# A601.net
KiCad netlist of a schematic drawn in EAGLE
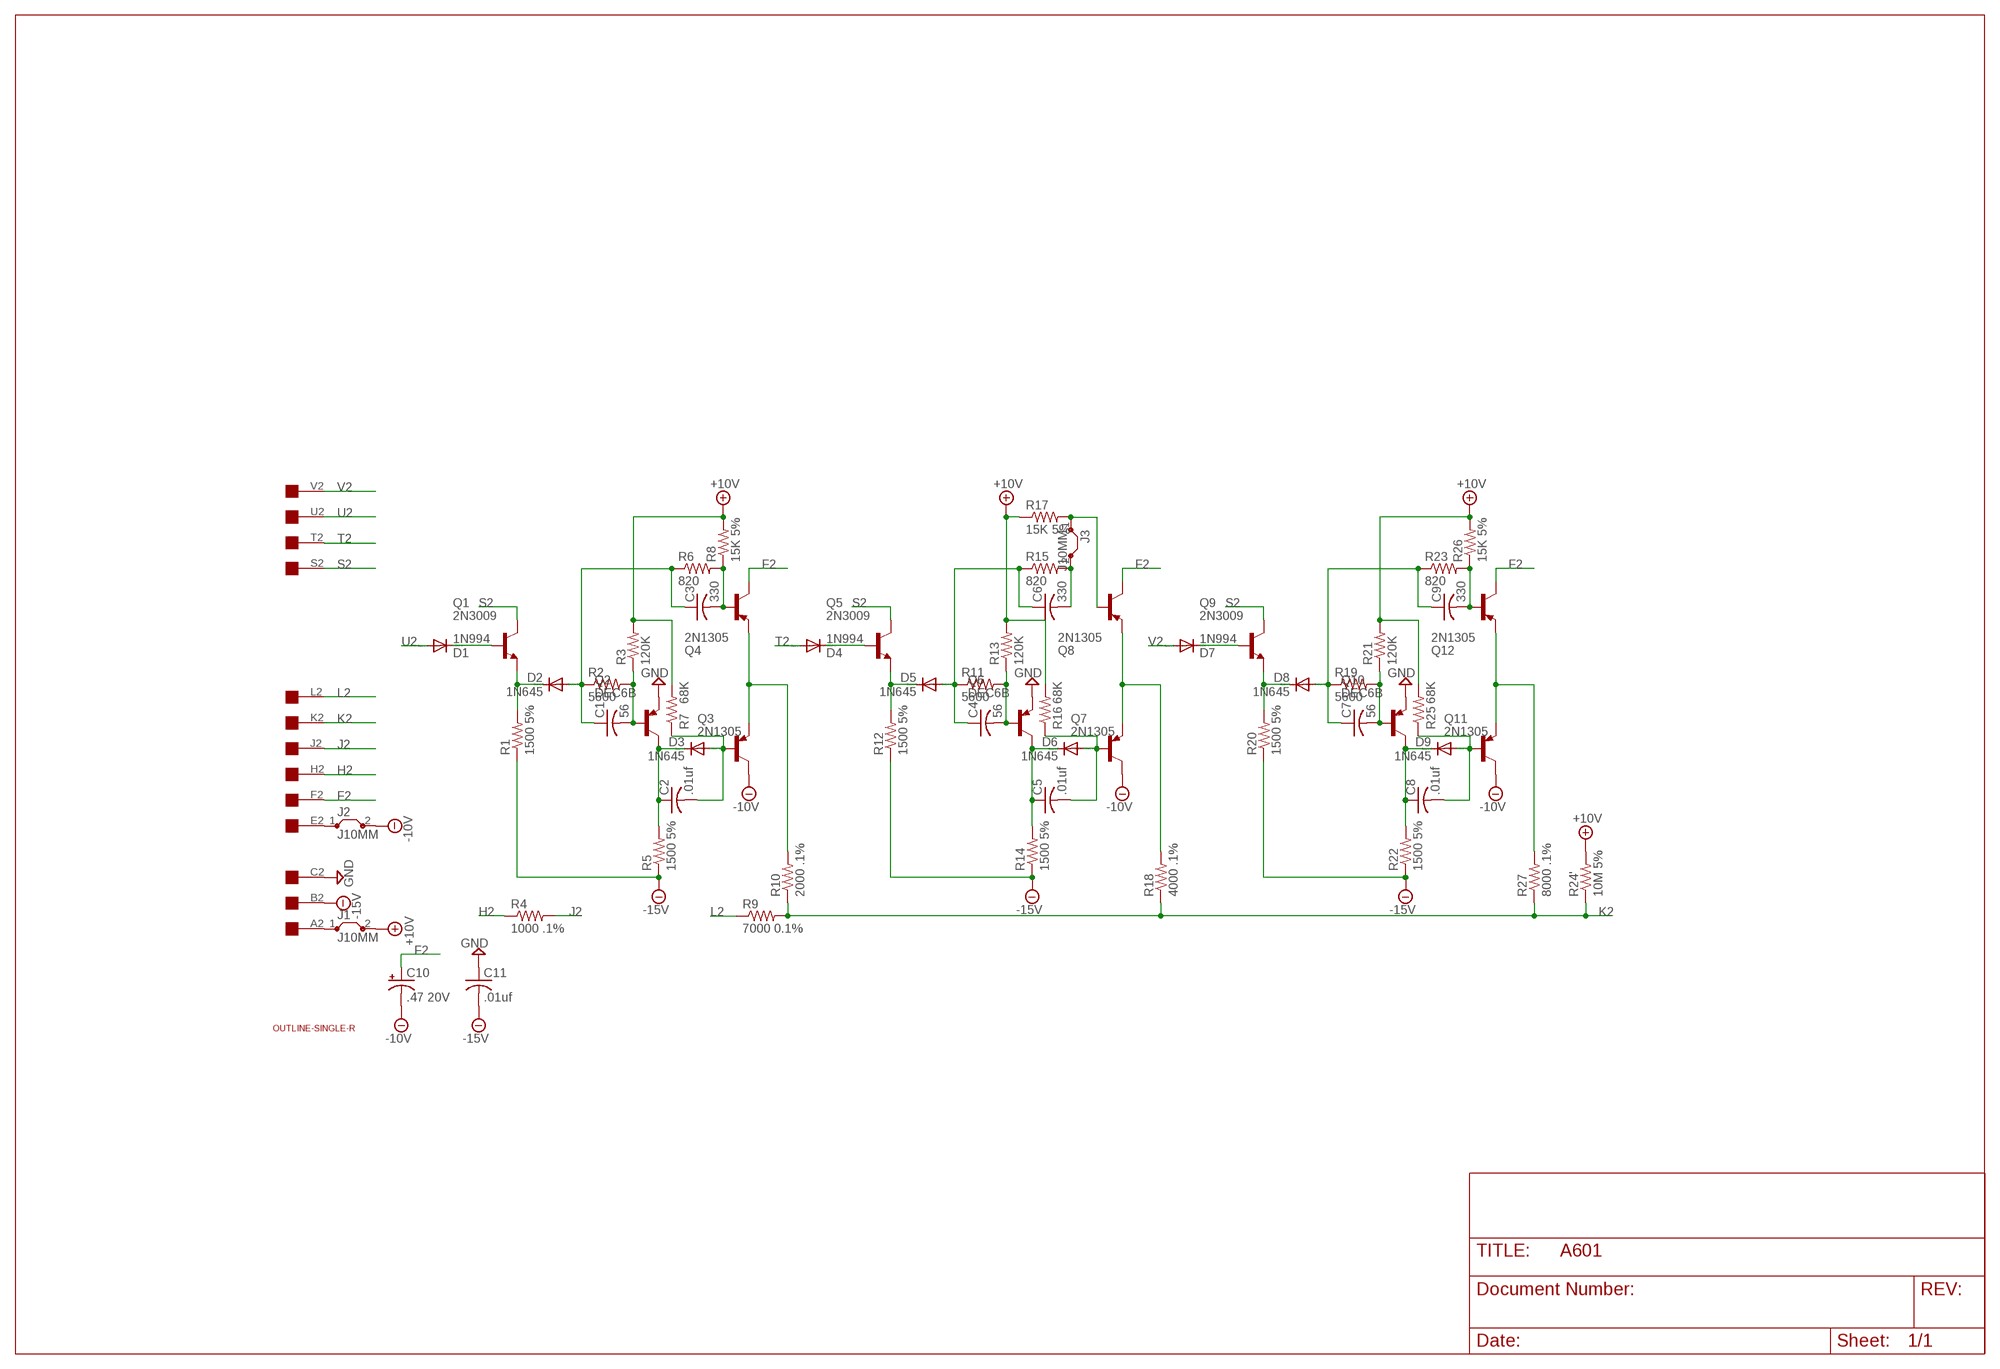
[diagram p0: schematic, sheet 1]

(export (version "E")
  (design (tool "Eeschema 10.0.6"))
  (components
    (comp (ref "C1")
      (value "56")
      (footprint "eagle-import:C075-032X103")
      (libsource (lib "eagle-import") (part "C-US075-032X103"))
    )
    (comp (ref "C2")
      (value ".01uf")
      (footprint "eagle-import:C050-025X075")
      (libsource (lib "eagle-import") (part "C-US050-025X075"))
    )
    (comp (ref "C3")
      (value "330")
      (footprint "eagle-import:C102-043X133")
      (libsource (lib "eagle-import") (part "C-US102-043X133"))
    )
    (comp (ref "C4")
      (value "56")
      (footprint "eagle-import:C075-032X103")
      (libsource (lib "eagle-import") (part "C-US075-032X103"))
    )
    (comp (ref "C5")
      (value ".01uf")
      (footprint "eagle-import:C050-025X075")
      (libsource (lib "eagle-import") (part "C-US050-025X075"))
    )
    (comp (ref "C6")
      (value "330")
      (footprint "eagle-import:C102-043X133")
      (libsource (lib "eagle-import") (part "C-US102-043X133"))
    )
    (comp (ref "C7")
      (value "56")
      (footprint "eagle-import:C075-032X103")
      (libsource (lib "eagle-import") (part "C-US075-032X103"))
    )
    (comp (ref "C8")
      (value ".01uf")
      (footprint "eagle-import:C050-025X075")
      (libsource (lib "eagle-import") (part "C-US050-025X075"))
    )
    (comp (ref "C9")
      (value "330")
      (footprint "eagle-import:C102-043X133")
      (libsource (lib "eagle-import") (part "C-US102-043X133"))
    )
    (comp (ref "C10")
      (value ".47 20V")
      (footprint "eagle-import:E22-6")
      (libsource (lib "eagle-import") (part "CPOL-USE22-6AXIAL"))
    )
    (comp (ref "C11")
      (value ".01uf")
      (footprint "eagle-import:C050-025X075")
      (libsource (lib "eagle-import") (part "C-US050-025X075"))
    )
    (comp (ref "D1")
      (value "1N994")
      (footprint "eagle-import:DO35-10")
      (libsource (lib "eagle-import") (part "1N4148DO35-10"))
    )
    (comp (ref "D2")
      (value "1N645")
      (footprint "eagle-import:DO35-10")
      (libsource (lib "eagle-import") (part "1N4148DO35-10"))
    )
    (comp (ref "D3")
      (value "1N645")
      (footprint "eagle-import:DO35-10")
      (libsource (lib "eagle-import") (part "1N4148DO35-10"))
    )
    (comp (ref "D4")
      (value "1N994")
      (footprint "eagle-import:DO35-10")
      (libsource (lib "eagle-import") (part "1N4148DO35-10"))
    )
    (comp (ref "D5")
      (value "1N645")
      (footprint "eagle-import:DO35-10")
      (libsource (lib "eagle-import") (part "1N4148DO35-10"))
    )
    (comp (ref "D6")
      (value "1N645")
      (footprint "eagle-import:DO35-10")
      (libsource (lib "eagle-import") (part "1N4148DO35-10"))
    )
    (comp (ref "D7")
      (value "1N994")
      (footprint "eagle-import:DO35-10")
      (libsource (lib "eagle-import") (part "1N4148DO35-10"))
    )
    (comp (ref "D8")
      (value "1N645")
      (footprint "eagle-import:DO35-10")
      (libsource (lib "eagle-import") (part "1N4148DO35-10"))
    )
    (comp (ref "D9")
      (value "1N645")
      (footprint "eagle-import:DO35-10")
      (libsource (lib "eagle-import") (part "1N4148DO35-10"))
    )
    (comp (ref "J1")
      (value "J10MM")
      (footprint "eagle-import:10")
      (libsource (lib "eagle-import") (part "J10MM"))
    )
    (comp (ref "J2")
      (value "J10MM")
      (footprint "eagle-import:10")
      (libsource (lib "eagle-import") (part "J10MM"))
    )
    (comp (ref "J3")
      (value "J10MM")
      (footprint "eagle-import:10")
      (libsource (lib "eagle-import") (part "J10MM"))
    )
    (comp (ref "Q1")
      (value "2N3009")
      (footprint "eagle-import:TO39")
      (libsource (lib "eagle-import") (part "-NPN-TO39-EBC2N1613"))
    )
    (comp (ref "Q2")
      (value "DEC6B")
      (footprint "eagle-import:TO39")
      (libsource (lib "eagle-import") (part "2N2904A"))
    )
    (comp (ref "Q3")
      (value "2N1305")
      (footprint "eagle-import:TO39")
      (libsource (lib "eagle-import") (part "2N2904A"))
    )
    (comp (ref "Q4")
      (value "2N1305")
      (footprint "eagle-import:TO39")
      (libsource (lib "eagle-import") (part "2N2904A"))
    )
    (comp (ref "Q5")
      (value "2N3009")
      (footprint "eagle-import:TO39")
      (libsource (lib "eagle-import") (part "-NPN-TO39-EBC2N1613"))
    )
    (comp (ref "Q6")
      (value "DEC6B")
      (footprint "eagle-import:TO39")
      (libsource (lib "eagle-import") (part "2N2904A"))
    )
    (comp (ref "Q7")
      (value "2N1305")
      (footprint "eagle-import:TO39")
      (libsource (lib "eagle-import") (part "2N2904A"))
    )
    (comp (ref "Q8")
      (value "2N1305")
      (footprint "eagle-import:TO39")
      (libsource (lib "eagle-import") (part "2N2904A"))
    )
    (comp (ref "Q9")
      (value "2N3009")
      (footprint "eagle-import:TO39")
      (libsource (lib "eagle-import") (part "-NPN-TO39-EBC2N1613"))
    )
    (comp (ref "Q10")
      (value "DEC6B")
      (footprint "eagle-import:TO39")
      (libsource (lib "eagle-import") (part "2N2904A"))
    )
    (comp (ref "Q11")
      (value "2N1305")
      (footprint "eagle-import:TO39")
      (libsource (lib "eagle-import") (part "2N2904A"))
    )
    (comp (ref "Q12")
      (value "2N1305")
      (footprint "eagle-import:TO39")
      (libsource (lib "eagle-import") (part "2N2904A"))
    )
    (comp (ref "R1")
      (value "1500 5%")
      (footprint "eagle-import:0207_10")
      (libsource (lib "eagle-import") (part "R-US_0207/10"))
    )
    (comp (ref "R2")
      (value "5600")
      (footprint "eagle-import:0207_10")
      (libsource (lib "eagle-import") (part "R-US_0207/10"))
    )
    (comp (ref "R3")
      (value "120K")
      (footprint "eagle-import:0207_10")
      (libsource (lib "eagle-import") (part "R-US_0207/10"))
    )
    (comp (ref "R4")
      (value "1000 .1%")
      (footprint "eagle-import:0309_12")
      (libsource (lib "eagle-import") (part "R-US_0309/12"))
    )
    (comp (ref "R5")
      (value "1500 5%")
      (footprint "eagle-import:0207_10")
      (libsource (lib "eagle-import") (part "R-US_0207/10"))
    )
    (comp (ref "R6")
      (value "820")
      (footprint "eagle-import:0207_10")
      (libsource (lib "eagle-import") (part "R-US_0207/10"))
    )
    (comp (ref "R7")
      (value "68K")
      (footprint "eagle-import:0207_10")
      (libsource (lib "eagle-import") (part "R-US_0207/10"))
    )
    (comp (ref "R8")
      (value "15K 5%")
      (footprint "eagle-import:0207_10")
      (libsource (lib "eagle-import") (part "R-US_0207/10"))
    )
    (comp (ref "R9")
      (value "7000 0.1%")
      (footprint "eagle-import:0309_12")
      (libsource (lib "eagle-import") (part "R-US_0309/12"))
    )
    (comp (ref "R10")
      (value "2000 .1%")
      (footprint "eagle-import:0309_12")
      (libsource (lib "eagle-import") (part "R-US_0309/12"))
    )
    (comp (ref "R11")
      (value "5600")
      (footprint "eagle-import:0207_10")
      (libsource (lib "eagle-import") (part "R-US_0207/10"))
    )
    (comp (ref "R12")
      (value "1500 5%")
      (footprint "eagle-import:0207_10")
      (libsource (lib "eagle-import") (part "R-US_0207/10"))
    )
    (comp (ref "R13")
      (value "120K")
      (footprint "eagle-import:0207_10")
      (libsource (lib "eagle-import") (part "R-US_0207/10"))
    )
    (comp (ref "R14")
      (value "1500 5%")
      (footprint "eagle-import:0207_10")
      (libsource (lib "eagle-import") (part "R-US_0207/10"))
    )
    (comp (ref "R15")
      (value "820")
      (footprint "eagle-import:0207_10")
      (libsource (lib "eagle-import") (part "R-US_0207/10"))
    )
    (comp (ref "R16")
      (value "68K")
      (footprint "eagle-import:0207_10")
      (libsource (lib "eagle-import") (part "R-US_0207/10"))
    )
    (comp (ref "R17")
      (value "15K 5%")
      (footprint "eagle-import:0207_10")
      (libsource (lib "eagle-import") (part "R-US_0207/10"))
    )
    (comp (ref "R18")
      (value "4000 .1%")
      (footprint "eagle-import:0309_12")
      (libsource (lib "eagle-import") (part "R-US_0309/12"))
    )
    (comp (ref "R19")
      (value "5600")
      (footprint "eagle-import:0207_10")
      (libsource (lib "eagle-import") (part "R-US_0207/10"))
    )
    (comp (ref "R20")
      (value "1500 5%")
      (footprint "eagle-import:0207_10")
      (libsource (lib "eagle-import") (part "R-US_0207/10"))
    )
    (comp (ref "R21")
      (value "120K")
      (footprint "eagle-import:0207_10")
      (libsource (lib "eagle-import") (part "R-US_0207/10"))
    )
    (comp (ref "R22")
      (value "1500 5%")
      (footprint "eagle-import:0207_10")
      (libsource (lib "eagle-import") (part "R-US_0207/10"))
    )
    (comp (ref "R23")
      (value "820")
      (footprint "eagle-import:0207_10")
      (libsource (lib "eagle-import") (part "R-US_0207/10"))
    )
    (comp (ref "R24'")
      (value "10M 5%")
      (footprint "eagle-import:0207_10")
      (libsource (lib "eagle-import") (part "R-US_0207/10"))
    )
    (comp (ref "R25")
      (value "68K")
      (footprint "eagle-import:0207_10")
      (libsource (lib "eagle-import") (part "R-US_0207/10"))
    )
    (comp (ref "R26")
      (value "15K 5%")
      (footprint "eagle-import:0207_10")
      (libsource (lib "eagle-import") (part "R-US_0207/10"))
    )
    (comp (ref "R27")
      (value "8000 .1%")
      (footprint "eagle-import:0309_12")
      (libsource (lib "eagle-import") (part "R-US_0309/12"))
    )
    (comp (ref "U$2")
      (value "OUTLINE-SINGLE-R")
      (footprint "eagle-import:SINGLE-R")
      (libsource (lib "eagle-import") (part "OUTLINE-SINGLE-R"))
    )
    (comp (ref "U$3")
      (value "EDGE-1")
      (footprint "eagle-import:EDGE-CON1")
      (libsource (lib "eagle-import") (part "EDGE-1"))
    )
  )
  (nets
    (net (code "1") (name "+10V") (class "Default")
      (node (ref "J1") (pin "2") (pinfunction "2_2") (pintype "passive"))
      (node (ref "R13") (pin "2") (pinfunction "2_2") (pintype "passive"))
      (node (ref "R16") (pin "2") (pinfunction "2_2") (pintype "passive"))
      (node (ref "R17") (pin "1") (pinfunction "1_1") (pintype "passive"))
      (node (ref "R21") (pin "2") (pinfunction "2_2") (pintype "passive"))
      (node (ref "R24'") (pin "2") (pinfunction "2_2") (pintype "passive"))
      (node (ref "R25") (pin "2") (pinfunction "2_2") (pintype "passive"))
      (node (ref "R26") (pin "2") (pinfunction "2_2") (pintype "passive"))
      (node (ref "R3") (pin "2") (pinfunction "2_2") (pintype "passive"))
      (node (ref "R7") (pin "2") (pinfunction "2_2") (pintype "passive"))
      (node (ref "R8") (pin "2") (pinfunction "2_2") (pintype "passive"))
    )
    (net (code "2") (name "-10V") (class "Default")
      (node (ref "C10") (pin "-") (pinfunction "-_-") (pintype "passive"))
      (node (ref "J2") (pin "2") (pinfunction "2_2") (pintype "passive"))
      (node (ref "Q11") (pin "3") (pinfunction "C_3") (pintype "passive"))
      (node (ref "Q3") (pin "3") (pinfunction "C_3") (pintype "passive"))
      (node (ref "Q7") (pin "3") (pinfunction "C_3") (pintype "passive"))
    )
    (net (code "3") (name "-15V") (class "Default")
      (node (ref "C11") (pin "2") (pinfunction "2_2") (pintype "passive"))
      (node (ref "R1") (pin "1") (pinfunction "1_1") (pintype "passive"))
      (node (ref "R12") (pin "1") (pinfunction "1_1") (pintype "passive"))
      (node (ref "R14") (pin "1") (pinfunction "1_1") (pintype "passive"))
      (node (ref "R20") (pin "1") (pinfunction "1_1") (pintype "passive"))
      (node (ref "R22") (pin "1") (pinfunction "1_1") (pintype "passive"))
      (node (ref "R5") (pin "1") (pinfunction "1_1") (pintype "passive"))
      (node (ref "U$3") (pin "B2") (pinfunction "1_B2") (pintype "bidirectional"))
    )
    (net (code "4") (name "/F2") (class "Default")
      (node (ref "C10") (pin "+") (pinfunction "+_+") (pintype "passive"))
      (node (ref "Q12") (pin "3") (pinfunction "C_3") (pintype "passive"))
      (node (ref "Q4") (pin "3") (pinfunction "C_3") (pintype "passive"))
      (node (ref "Q8") (pin "3") (pinfunction "C_3") (pintype "passive"))
      (node (ref "U$3") (pin "F2") (pinfunction "1_F2") (pintype "bidirectional"))
    )
    (net (code "5") (name "/H2") (class "Default")
      (node (ref "R4") (pin "1") (pinfunction "1_1") (pintype "passive"))
      (node (ref "U$3") (pin "H2") (pinfunction "1_H2") (pintype "bidirectional"))
    )
    (net (code "6") (name "/J2") (class "Default")
      (node (ref "R4") (pin "2") (pinfunction "2_2") (pintype "passive"))
      (node (ref "U$3") (pin "J2") (pinfunction "1_J2") (pintype "bidirectional"))
    )
    (net (code "7") (name "/K2") (class "Default")
      (node (ref "R10") (pin "1") (pinfunction "1_1") (pintype "passive"))
      (node (ref "R18") (pin "1") (pinfunction "1_1") (pintype "passive"))
      (node (ref "R24'") (pin "1") (pinfunction "1_1") (pintype "passive"))
      (node (ref "R27") (pin "1") (pinfunction "1_1") (pintype "passive"))
      (node (ref "R9") (pin "2") (pinfunction "2_2") (pintype "passive"))
      (node (ref "U$3") (pin "K2") (pinfunction "1_K2") (pintype "bidirectional"))
    )
    (net (code "8") (name "/L2") (class "Default")
      (node (ref "R9") (pin "1") (pinfunction "1_1") (pintype "passive"))
      (node (ref "U$3") (pin "L2") (pinfunction "1_L2") (pintype "bidirectional"))
    )
    (net (code "9") (name "/S2") (class "Default")
      (node (ref "Q1") (pin "3") (pinfunction "C_3") (pintype "passive"))
      (node (ref "Q5") (pin "3") (pinfunction "C_3") (pintype "passive"))
      (node (ref "Q9") (pin "3") (pinfunction "C_3") (pintype "passive"))
      (node (ref "U$3") (pin "S2") (pinfunction "1_S2") (pintype "bidirectional"))
    )
    (net (code "10") (name "/T2") (class "Default")
      (node (ref "D4") (pin "A") (pinfunction "A_A") (pintype "passive"))
      (node (ref "U$3") (pin "T2") (pinfunction "1_T2") (pintype "bidirectional"))
    )
    (net (code "11") (name "/U2") (class "Default")
      (node (ref "D1") (pin "A") (pinfunction "A_A") (pintype "passive"))
      (node (ref "U$3") (pin "U2") (pinfunction "1_U2") (pintype "bidirectional"))
    )
    (net (code "12") (name "/V2") (class "Default")
      (node (ref "D7") (pin "A") (pinfunction "A_A") (pintype "passive"))
      (node (ref "U$3") (pin "V2") (pinfunction "1_V2") (pintype "bidirectional"))
    )
    (net (code "13") (name "GND") (class "Default")
      (node (ref "C11") (pin "1") (pinfunction "1_1") (pintype "passive"))
      (node (ref "Q10") (pin "1") (pinfunction "E_1") (pintype "passive"))
      (node (ref "Q2") (pin "1") (pinfunction "E_1") (pintype "passive"))
      (node (ref "Q6") (pin "1") (pinfunction "E_1") (pintype "passive"))
      (node (ref "U$3") (pin "C2") (pinfunction "1_C2") (pintype "bidirectional"))
    )
    (net (code "14") (name "Net-(C1-Pad1)") (class "Default")
      (node (ref "C1") (pin "1") (pinfunction "1_1") (pintype "passive"))
      (node (ref "C3") (pin "1") (pinfunction "1_1") (pintype "passive"))
      (node (ref "D2") (pin "A") (pinfunction "A_A") (pintype "passive"))
      (node (ref "R2") (pin "1") (pinfunction "1_1") (pintype "passive"))
      (node (ref "R6") (pin "1") (pinfunction "1_1") (pintype "passive"))
    )
    (net (code "15") (name "Net-(C4-Pad1)") (class "Default")
      (node (ref "C4") (pin "1") (pinfunction "1_1") (pintype "passive"))
      (node (ref "C6") (pin "1") (pinfunction "1_1") (pintype "passive"))
      (node (ref "D5") (pin "A") (pinfunction "A_A") (pintype "passive"))
      (node (ref "R11") (pin "1") (pinfunction "1_1") (pintype "passive"))
      (node (ref "R15") (pin "1") (pinfunction "1_1") (pintype "passive"))
    )
    (net (code "16") (name "Net-(C6-Pad2)") (class "Default")
      (node (ref "C6") (pin "2") (pinfunction "2_2") (pintype "passive"))
      (node (ref "J3") (pin "2") (pinfunction "2_2") (pintype "passive"))
      (node (ref "R15") (pin "2") (pinfunction "2_2") (pintype "passive"))
    )
    (net (code "17") (name "Net-(C7-Pad1)") (class "Default")
      (node (ref "C7") (pin "1") (pinfunction "1_1") (pintype "passive"))
      (node (ref "C9") (pin "1") (pinfunction "1_1") (pintype "passive"))
      (node (ref "D8") (pin "A") (pinfunction "A_A") (pintype "passive"))
      (node (ref "R19") (pin "1") (pinfunction "1_1") (pintype "passive"))
      (node (ref "R23") (pin "1") (pinfunction "1_1") (pintype "passive"))
    )
    (net (code "18") (name "Net-(Q1-B)") (class "Default")
      (node (ref "D1") (pin "C") (pinfunction "C_C") (pintype "passive"))
      (node (ref "Q1") (pin "2") (pinfunction "B_2") (pintype "passive"))
    )
    (net (code "19") (name "Net-(Q1-E)") (class "Default")
      (node (ref "D2") (pin "C") (pinfunction "C_C") (pintype "passive"))
      (node (ref "Q1") (pin "1") (pinfunction "E_1") (pintype "passive"))
      (node (ref "R1") (pin "2") (pinfunction "2_2") (pintype "passive"))
    )
    (net (code "20") (name "Net-(Q2-B)") (class "Default")
      (node (ref "C1") (pin "2") (pinfunction "2_2") (pintype "passive"))
      (node (ref "Q2") (pin "2") (pinfunction "B_2") (pintype "passive"))
      (node (ref "R2") (pin "2") (pinfunction "2_2") (pintype "passive"))
      (node (ref "R3") (pin "1") (pinfunction "1_1") (pintype "passive"))
    )
    (net (code "21") (name "Net-(Q2-C)") (class "Default")
      (node (ref "C2") (pin "1") (pinfunction "1_1") (pintype "passive"))
      (node (ref "D3") (pin "C") (pinfunction "C_C") (pintype "passive"))
      (node (ref "Q2") (pin "3") (pinfunction "C_3") (pintype "passive"))
      (node (ref "R5") (pin "2") (pinfunction "2_2") (pintype "passive"))
    )
    (net (code "22") (name "Net-(Q3-B)") (class "Default")
      (node (ref "C2") (pin "2") (pinfunction "2_2") (pintype "passive"))
      (node (ref "D3") (pin "A") (pinfunction "A_A") (pintype "passive"))
      (node (ref "Q3") (pin "2") (pinfunction "B_2") (pintype "passive"))
      (node (ref "R7") (pin "1") (pinfunction "1_1") (pintype "passive"))
    )
    (net (code "23") (name "Net-(Q3-E)") (class "Default")
      (node (ref "Q3") (pin "1") (pinfunction "E_1") (pintype "passive"))
      (node (ref "Q4") (pin "1") (pinfunction "E_1") (pintype "passive"))
      (node (ref "R10") (pin "2") (pinfunction "2_2") (pintype "passive"))
    )
    (net (code "24") (name "Net-(Q4-B)") (class "Default")
      (node (ref "C3") (pin "2") (pinfunction "2_2") (pintype "passive"))
      (node (ref "Q4") (pin "2") (pinfunction "B_2") (pintype "passive"))
      (node (ref "R6") (pin "2") (pinfunction "2_2") (pintype "passive"))
      (node (ref "R8") (pin "1") (pinfunction "1_1") (pintype "passive"))
    )
    (net (code "25") (name "Net-(Q5-B)") (class "Default")
      (node (ref "D4") (pin "C") (pinfunction "C_C") (pintype "passive"))
      (node (ref "Q5") (pin "2") (pinfunction "B_2") (pintype "passive"))
    )
    (net (code "26") (name "Net-(Q5-E)") (class "Default")
      (node (ref "D5") (pin "C") (pinfunction "C_C") (pintype "passive"))
      (node (ref "Q5") (pin "1") (pinfunction "E_1") (pintype "passive"))
      (node (ref "R12") (pin "2") (pinfunction "2_2") (pintype "passive"))
    )
    (net (code "27") (name "Net-(Q6-B)") (class "Default")
      (node (ref "C4") (pin "2") (pinfunction "2_2") (pintype "passive"))
      (node (ref "Q6") (pin "2") (pinfunction "B_2") (pintype "passive"))
      (node (ref "R11") (pin "2") (pinfunction "2_2") (pintype "passive"))
      (node (ref "R13") (pin "1") (pinfunction "1_1") (pintype "passive"))
    )
    (net (code "28") (name "Net-(Q6-C)") (class "Default")
      (node (ref "C5") (pin "1") (pinfunction "1_1") (pintype "passive"))
      (node (ref "D6") (pin "C") (pinfunction "C_C") (pintype "passive"))
      (node (ref "Q6") (pin "3") (pinfunction "C_3") (pintype "passive"))
      (node (ref "R14") (pin "2") (pinfunction "2_2") (pintype "passive"))
    )
    (net (code "29") (name "Net-(Q7-B)") (class "Default")
      (node (ref "C5") (pin "2") (pinfunction "2_2") (pintype "passive"))
      (node (ref "D6") (pin "A") (pinfunction "A_A") (pintype "passive"))
      (node (ref "Q7") (pin "2") (pinfunction "B_2") (pintype "passive"))
      (node (ref "R16") (pin "1") (pinfunction "1_1") (pintype "passive"))
    )
    (net (code "30") (name "Net-(Q7-E)") (class "Default")
      (node (ref "Q7") (pin "1") (pinfunction "E_1") (pintype "passive"))
      (node (ref "Q8") (pin "1") (pinfunction "E_1") (pintype "passive"))
      (node (ref "R18") (pin "2") (pinfunction "2_2") (pintype "passive"))
    )
    (net (code "31") (name "Net-(Q8-B)") (class "Default")
      (node (ref "J3") (pin "1") (pinfunction "1_1") (pintype "passive"))
      (node (ref "Q8") (pin "2") (pinfunction "B_2") (pintype "passive"))
      (node (ref "R17") (pin "2") (pinfunction "2_2") (pintype "passive"))
    )
    (net (code "32") (name "Net-(Q9-B)") (class "Default")
      (node (ref "D7") (pin "C") (pinfunction "C_C") (pintype "passive"))
      (node (ref "Q9") (pin "2") (pinfunction "B_2") (pintype "passive"))
    )
    (net (code "33") (name "Net-(Q9-E)") (class "Default")
      (node (ref "D8") (pin "C") (pinfunction "C_C") (pintype "passive"))
      (node (ref "Q9") (pin "1") (pinfunction "E_1") (pintype "passive"))
      (node (ref "R20") (pin "2") (pinfunction "2_2") (pintype "passive"))
    )
    (net (code "34") (name "Net-(Q10-B)") (class "Default")
      (node (ref "C7") (pin "2") (pinfunction "2_2") (pintype "passive"))
      (node (ref "Q10") (pin "2") (pinfunction "B_2") (pintype "passive"))
      (node (ref "R19") (pin "2") (pinfunction "2_2") (pintype "passive"))
      (node (ref "R21") (pin "1") (pinfunction "1_1") (pintype "passive"))
    )
    (net (code "35") (name "Net-(Q10-C)") (class "Default")
      (node (ref "C8") (pin "1") (pinfunction "1_1") (pintype "passive"))
      (node (ref "D9") (pin "C") (pinfunction "C_C") (pintype "passive"))
      (node (ref "Q10") (pin "3") (pinfunction "C_3") (pintype "passive"))
      (node (ref "R22") (pin "2") (pinfunction "2_2") (pintype "passive"))
    )
    (net (code "36") (name "Net-(Q11-B)") (class "Default")
      (node (ref "C8") (pin "2") (pinfunction "2_2") (pintype "passive"))
      (node (ref "D9") (pin "A") (pinfunction "A_A") (pintype "passive"))
      (node (ref "Q11") (pin "2") (pinfunction "B_2") (pintype "passive"))
      (node (ref "R25") (pin "1") (pinfunction "1_1") (pintype "passive"))
    )
    (net (code "37") (name "Net-(Q11-E)") (class "Default")
      (node (ref "Q11") (pin "1") (pinfunction "E_1") (pintype "passive"))
      (node (ref "Q12") (pin "1") (pinfunction "E_1") (pintype "passive"))
      (node (ref "R27") (pin "2") (pinfunction "2_2") (pintype "passive"))
    )
    (net (code "38") (name "Net-(Q12-B)") (class "Default")
      (node (ref "C9") (pin "2") (pinfunction "2_2") (pintype "passive"))
      (node (ref "Q12") (pin "2") (pinfunction "B_2") (pintype "passive"))
      (node (ref "R23") (pin "2") (pinfunction "2_2") (pintype "passive"))
      (node (ref "R26") (pin "1") (pinfunction "1_1") (pintype "passive"))
    )
    (net (code "39") (name "Net-(U$3A-1)") (class "Default")
      (node (ref "J1") (pin "1") (pinfunction "1_1") (pintype "passive"))
      (node (ref "U$3") (pin "A2") (pinfunction "1_A2") (pintype "bidirectional"))
    )
    (net (code "40") (name "Net-(U$3E-1)") (class "Default")
      (node (ref "J2") (pin "1") (pinfunction "1_1") (pintype "passive"))
      (node (ref "U$3") (pin "E2") (pinfunction "1_E2") (pintype "bidirectional"))
    )
  )
)
